# Intf_PCB.net
KiCad netlist of a schematic drawn in Altium Designer
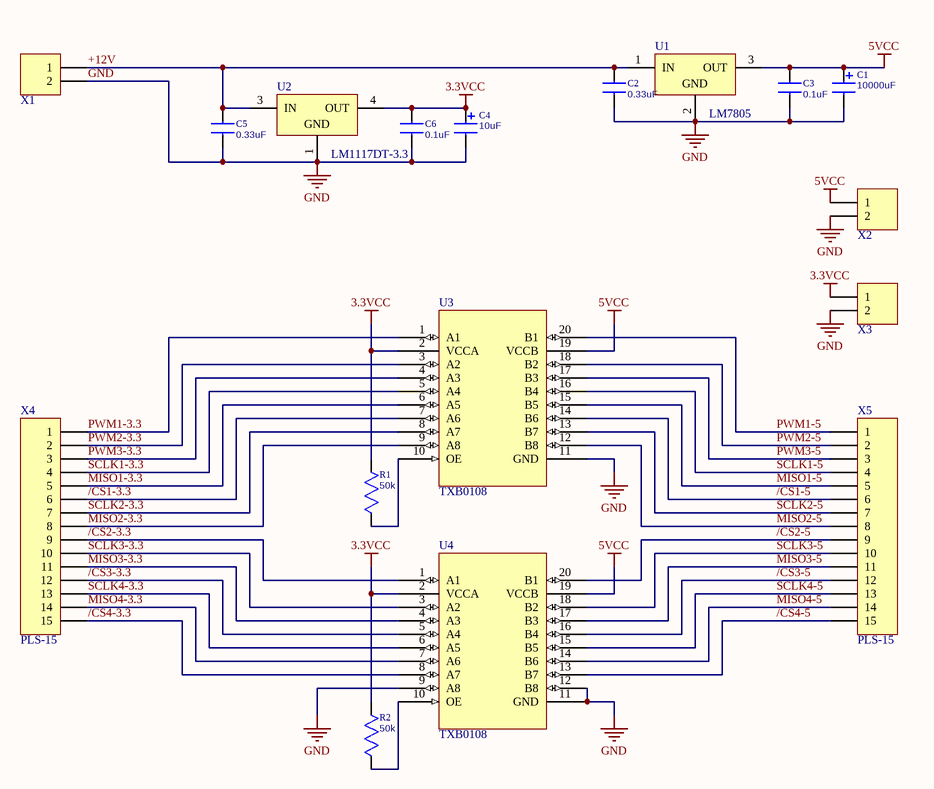
[diagram p0: Intf_PCB.SchDoc]

(export (version "E")
  (design (tool "Eeschema 10.0.6"))
  (components
    (comp (ref "C1")
      (value "10000uF")
      (footprint "CAP470X25V")
      (description "Capacitor")
      (libsource (lib "AX_Altium_v2.3") (part "C_10_12_5mm"))
    )
    (comp (ref "C2")
      (value "0.33uF")
      (footprint "C_1206")
      (description "Capacitor")
      (libsource (lib "AX_Altium_v2.3") (part "C1206"))
    )
    (comp (ref "C3")
      (value "0.1uF")
      (footprint "C_1206")
      (description "Capacitor")
      (libsource (lib "AX_Altium_v2.3") (part "C1206"))
    )
    (comp (ref "C4")
      (value "10uF")
      (footprint "CAP470X25V")
      (description "Capacitor")
      (libsource (lib "AX_Altium_v2.3") (part "C_10_12_5mm"))
    )
    (comp (ref "C5")
      (value "0.33uF")
      (footprint "C_1206")
      (description "Capacitor")
      (libsource (lib "AX_Altium_v2.3") (part "C1206"))
    )
    (comp (ref "C6")
      (value "0.1uF")
      (footprint "C_1206")
      (description "Capacitor")
      (libsource (lib "AX_Altium_v2.3") (part "C1206"))
    )
    (comp (ref "R1")
      (value "50k")
      (footprint "R_1206")
      (description "Resistor")
      (libsource (lib "AX_Altium_v2.3") (part "R1206"))
    )
    (comp (ref "R2")
      (value "50k")
      (footprint "R_1206")
      (description "Resistor")
      (libsource (lib "AX_Altium_v2.3") (part "R1206"))
    )
    (comp (ref "U1")
      (value "LM7805")
      (footprint "T03B")
      (description "3-Terminal Positive Voltage Regulators")
      (fields
        (field (name "PARTNUMBER") "LM78M05CT")
        (field (name "MANUFACTURER") "National Semiconductor")
        (field (name "PUBLISHER") "Altium Limited")
      )
      (libsource (lib "NSC LDO") (part "LM78M05CT"))
    )
    (comp (ref "U2")
      (value "LM1117DT-3.3")
      (footprint "TD03B_M")
      (description "800mA Low-Dropout Linear Regulator")
      (fields
        (field (name "MANUFACTURER") "National Semiconductor")
        (field (name "DIGIKEYPARTNUMBER") "LM1117DT-3.3-ND")
        (field (name "PUBLISHER") "Altium Limited")
      )
      (libsource (lib "NSC LDO") (part "LM1117DT-3.3"))
    )
    (comp (ref "U3")
      (value "TXB0108")
      (footprint "TSOP65P640X120-20N")
      (libsource (lib "Add_lib") (part "TXB0108"))
    )
    (comp (ref "U4")
      (value "TXB0108")
      (footprint "TSOP65P640X120-20N")
      (libsource (lib "Add_lib") (part "TXB0108"))
    )
    (comp (ref "X1")
      (value "PWL-2")
      (footprint "15EDGVC")
      (description "Header, 2-Pin")
      (fields (field (name "PUBLISHER") "Altium Limited"))
      (libsource (lib "") (part "PWL-2_1"))
    )
    (comp (ref "X2")
      (value "PWL-2")
      (footprint "15EDGVC")
      (description "Header, 2-Pin")
      (fields (field (name "PUBLISHER") "Altium Limited"))
      (libsource (lib "AX_Altium_v2.3") (part "PWL-2"))
    )
    (comp (ref "X3")
      (value "PWL-2")
      (footprint "15EDGVC")
      (description "Header, 2-Pin")
      (fields (field (name "PUBLISHER") "Altium Limited"))
      (libsource (lib "AX_Altium_v2.3") (part "PWL-2"))
    )
    (comp (ref "X4")
      (value "PLS-15")
      (footprint "PLS-15-3D")
      (description "Header, 15-Pin")
      (fields (field (name "PUBLISHER") "Altium Limited"))
      (libsource (lib "") (part "PLS-15_1"))
    )
    (comp (ref "X5")
      (value "PLS-15")
      (footprint "PLS-15-3D")
      (description "Header, 15-Pin")
      (fields (field (name "PUBLISHER") "Altium Limited"))
      (libsource (lib "AX_Altium_v2.3") (part "PLS-15"))
    )
  )
  (nets
    (net (code "1") (name "/+12V") (class "Default")
      (node (ref "C2") (pin "1") (pintype "passive"))
      (node (ref "C5") (pin "1") (pintype "passive"))
      (node (ref "U1") (pin "1") (pinfunction "IN_1") (pintype "power_in"))
      (node (ref "U2") (pin "3") (pinfunction "IN_3") (pintype "power_in"))
      (node (ref "X1") (pin "1") (pinfunction "1_1") (pintype "passive"))
    )
    (net (code "2") (name "/MISO1-3.3") (class "Default")
      (node (ref "U3") (pin "6") (pinfunction "A5_6") (pintype "bidirectional"))
      (node (ref "X4") (pin "5") (pinfunction "5_5") (pintype "passive"))
    )
    (net (code "3") (name "/MISO1-5") (class "Default")
      (node (ref "U3") (pin "15") (pinfunction "B5_15") (pintype "bidirectional"))
      (node (ref "X5") (pin "5") (pinfunction "5_5") (pintype "passive"))
    )
    (net (code "4") (name "/MISO2-3.3") (class "Default")
      (node (ref "U3") (pin "9") (pinfunction "A8_9") (pintype "bidirectional"))
      (node (ref "X4") (pin "8") (pinfunction "8_8") (pintype "passive"))
    )
    (net (code "5") (name "/MISO2-5") (class "Default")
      (node (ref "U3") (pin "12") (pinfunction "B8_12") (pintype "bidirectional"))
      (node (ref "X5") (pin "8") (pinfunction "8_8") (pintype "passive"))
    )
    (net (code "6") (name "/MISO3-3.3") (class "Default")
      (node (ref "U4") (pin "4") (pinfunction "A3_4") (pintype "bidirectional"))
      (node (ref "X4") (pin "11") (pinfunction "11_11") (pintype "passive"))
    )
    (net (code "7") (name "/MISO3-5") (class "Default")
      (node (ref "U4") (pin "17") (pinfunction "B3_17") (pintype "bidirectional"))
      (node (ref "X5") (pin "11") (pinfunction "11_11") (pintype "passive"))
    )
    (net (code "8") (name "/MISO4-3.3") (class "Default")
      (node (ref "U4") (pin "7") (pinfunction "A6_7") (pintype "bidirectional"))
      (node (ref "X4") (pin "14") (pinfunction "14_14") (pintype "passive"))
    )
    (net (code "9") (name "/MISO4-5") (class "Default")
      (node (ref "U4") (pin "14") (pinfunction "B6_14") (pintype "bidirectional"))
      (node (ref "X5") (pin "14") (pinfunction "14_14") (pintype "passive"))
    )
    (net (code "10") (name "/PWM1-3.3") (class "Default")
      (node (ref "U3") (pin "1") (pinfunction "A1_1") (pintype "bidirectional"))
      (node (ref "X4") (pin "1") (pinfunction "1_1") (pintype "passive"))
    )
    (net (code "11") (name "/PWM1-5") (class "Default")
      (node (ref "U3") (pin "20") (pinfunction "B1_20") (pintype "bidirectional"))
      (node (ref "X5") (pin "1") (pinfunction "1_1") (pintype "passive"))
    )
    (net (code "12") (name "/PWM2-3.3") (class "Default")
      (node (ref "U3") (pin "3") (pinfunction "A2_3") (pintype "bidirectional"))
      (node (ref "X4") (pin "2") (pinfunction "2_2") (pintype "passive"))
    )
    (net (code "13") (name "/PWM2-5") (class "Default")
      (node (ref "U3") (pin "18") (pinfunction "B2_18") (pintype "bidirectional"))
      (node (ref "X5") (pin "2") (pinfunction "2_2") (pintype "passive"))
    )
    (net (code "14") (name "/PWM3-3.3") (class "Default")
      (node (ref "U3") (pin "4") (pinfunction "A3_4") (pintype "bidirectional"))
      (node (ref "X4") (pin "3") (pinfunction "3_3") (pintype "passive"))
    )
    (net (code "15") (name "/PWM3-5") (class "Default")
      (node (ref "U3") (pin "17") (pinfunction "B3_17") (pintype "bidirectional"))
      (node (ref "X5") (pin "3") (pinfunction "3_3") (pintype "passive"))
    )
    (net (code "16") (name "/SCLK1-3.3") (class "Default")
      (node (ref "U3") (pin "5") (pinfunction "A4_5") (pintype "bidirectional"))
      (node (ref "X4") (pin "4") (pinfunction "4_4") (pintype "passive"))
    )
    (net (code "17") (name "/SCLK1-5") (class "Default")
      (node (ref "U3") (pin "16") (pinfunction "B4_16") (pintype "bidirectional"))
      (node (ref "X5") (pin "4") (pinfunction "4_4") (pintype "passive"))
    )
    (net (code "18") (name "/SCLK2-3.3") (class "Default")
      (node (ref "U3") (pin "8") (pinfunction "A7_8") (pintype "bidirectional"))
      (node (ref "X4") (pin "7") (pinfunction "7_7") (pintype "passive"))
    )
    (net (code "19") (name "/SCLK2-5") (class "Default")
      (node (ref "U3") (pin "13") (pinfunction "B7_13") (pintype "bidirectional"))
      (node (ref "X5") (pin "7") (pinfunction "7_7") (pintype "passive"))
    )
    (net (code "20") (name "/SCLK3-3.3") (class "Default")
      (node (ref "U4") (pin "3") (pinfunction "A2_3") (pintype "bidirectional"))
      (node (ref "X4") (pin "10") (pinfunction "10_10") (pintype "passive"))
    )
    (net (code "21") (name "/SCLK3-5") (class "Default")
      (node (ref "U4") (pin "18") (pinfunction "B2_18") (pintype "bidirectional"))
      (node (ref "X5") (pin "10") (pinfunction "10_10") (pintype "passive"))
    )
    (net (code "22") (name "/SCLK4-3.3") (class "Default")
      (node (ref "U4") (pin "6") (pinfunction "A5_6") (pintype "bidirectional"))
      (node (ref "X4") (pin "13") (pinfunction "13_13") (pintype "passive"))
    )
    (net (code "23") (name "/SCLK4-5") (class "Default")
      (node (ref "U4") (pin "15") (pinfunction "B5_15") (pintype "bidirectional"))
      (node (ref "X5") (pin "13") (pinfunction "13_13") (pintype "passive"))
    )
    (net (code "24") (name "/{slash}CS1-3.3") (class "Default")
      (node (ref "U3") (pin "7") (pinfunction "A6_7") (pintype "bidirectional"))
      (node (ref "X4") (pin "6") (pinfunction "6_6") (pintype "passive"))
    )
    (net (code "25") (name "/{slash}CS1-5") (class "Default")
      (node (ref "U3") (pin "14") (pinfunction "B6_14") (pintype "bidirectional"))
      (node (ref "X5") (pin "6") (pinfunction "6_6") (pintype "passive"))
    )
    (net (code "26") (name "/{slash}CS2-3.3") (class "Default")
      (node (ref "U4") (pin "1") (pinfunction "A1_1") (pintype "bidirectional"))
      (node (ref "X4") (pin "9") (pinfunction "9_9") (pintype "passive"))
    )
    (net (code "27") (name "/{slash}CS2-5") (class "Default")
      (node (ref "U4") (pin "20") (pinfunction "B1_20") (pintype "bidirectional"))
      (node (ref "X5") (pin "9") (pinfunction "9_9") (pintype "passive"))
    )
    (net (code "28") (name "/{slash}CS3-3.3") (class "Default")
      (node (ref "U4") (pin "5") (pinfunction "A4_5") (pintype "bidirectional"))
      (node (ref "X4") (pin "12") (pinfunction "12_12") (pintype "passive"))
    )
    (net (code "29") (name "/{slash}CS3-5") (class "Default")
      (node (ref "U4") (pin "16") (pinfunction "B4_16") (pintype "bidirectional"))
      (node (ref "X5") (pin "12") (pinfunction "12_12") (pintype "passive"))
    )
    (net (code "30") (name "/{slash}CS4-3.3") (class "Default")
      (node (ref "U4") (pin "8") (pinfunction "A7_8") (pintype "bidirectional"))
      (node (ref "X4") (pin "15") (pinfunction "15_15") (pintype "passive"))
    )
    (net (code "31") (name "/{slash}CS4-5") (class "Default")
      (node (ref "U4") (pin "13") (pinfunction "B7_13") (pintype "bidirectional"))
      (node (ref "X5") (pin "15") (pinfunction "15_15") (pintype "passive"))
    )
    (net (code "32") (name "3.3VCC") (class "Default")
      (node (ref "C4") (pin "1") (pinfunction "1_1") (pintype "passive"))
      (node (ref "C6") (pin "1") (pintype "passive"))
      (node (ref "R1") (pin "1") (pintype "passive"))
      (node (ref "R2") (pin "1") (pintype "passive"))
      (node (ref "U2") (pin "4") (pinfunction "OUT_4") (pintype "power_in"))
      (node (ref "U3") (pin "2") (pinfunction "VCCA_2") (pintype "passive"))
      (node (ref "U4") (pin "2") (pinfunction "VCCA_2") (pintype "passive"))
      (node (ref "X3") (pin "1") (pinfunction "1_1") (pintype "passive"))
    )
    (net (code "33") (name "5VCC") (class "Default")
      (node (ref "C1") (pin "1") (pinfunction "1_1") (pintype "passive"))
      (node (ref "C3") (pin "1") (pintype "passive"))
      (node (ref "U1") (pin "3") (pinfunction "OUT_3") (pintype "power_in"))
      (node (ref "U3") (pin "19") (pinfunction "VCCB_19") (pintype "passive"))
      (node (ref "U4") (pin "19") (pinfunction "VCCB_19") (pintype "passive"))
      (node (ref "X2") (pin "1") (pinfunction "1_1") (pintype "passive"))
    )
    (net (code "34") (name "GND") (class "Default")
      (node (ref "C1") (pin "2") (pinfunction "2_2") (pintype "passive"))
      (node (ref "C2") (pin "2") (pintype "passive"))
      (node (ref "C3") (pin "2") (pintype "passive"))
      (node (ref "C4") (pin "2") (pinfunction "2_2") (pintype "passive"))
      (node (ref "C5") (pin "2") (pintype "passive"))
      (node (ref "C6") (pin "2") (pintype "passive"))
      (node (ref "U1") (pin "2") (pinfunction "GND_2") (pintype "power_in"))
      (node (ref "U2") (pin "1") (pinfunction "GND_1") (pintype "power_in"))
      (node (ref "U3") (pin "11") (pinfunction "GND_11") (pintype "passive"))
      (node (ref "U4") (pin "11") (pinfunction "GND_11") (pintype "passive"))
      (node (ref "U4") (pin "12") (pinfunction "B8_12") (pintype "bidirectional"))
      (node (ref "U4") (pin "9") (pinfunction "A8_9") (pintype "bidirectional"))
      (node (ref "X1") (pin "2") (pinfunction "2_2") (pintype "passive"))
      (node (ref "X2") (pin "2") (pinfunction "2_2") (pintype "passive"))
      (node (ref "X3") (pin "2") (pinfunction "2_2") (pintype "passive"))
    )
    (net (code "35") (name "Net-(U3-OE)") (class "Default")
      (node (ref "R1") (pin "2") (pintype "passive"))
      (node (ref "U3") (pin "10") (pinfunction "OE_10") (pintype "input"))
    )
    (net (code "36") (name "Net-(U4-OE)") (class "Default")
      (node (ref "R2") (pin "2") (pintype "passive"))
      (node (ref "U4") (pin "10") (pinfunction "OE_10") (pintype "input"))
    )
  )
)
